# Tasmodul_WLED.net
KiCad netlist of a schematic drawn in EAGLE
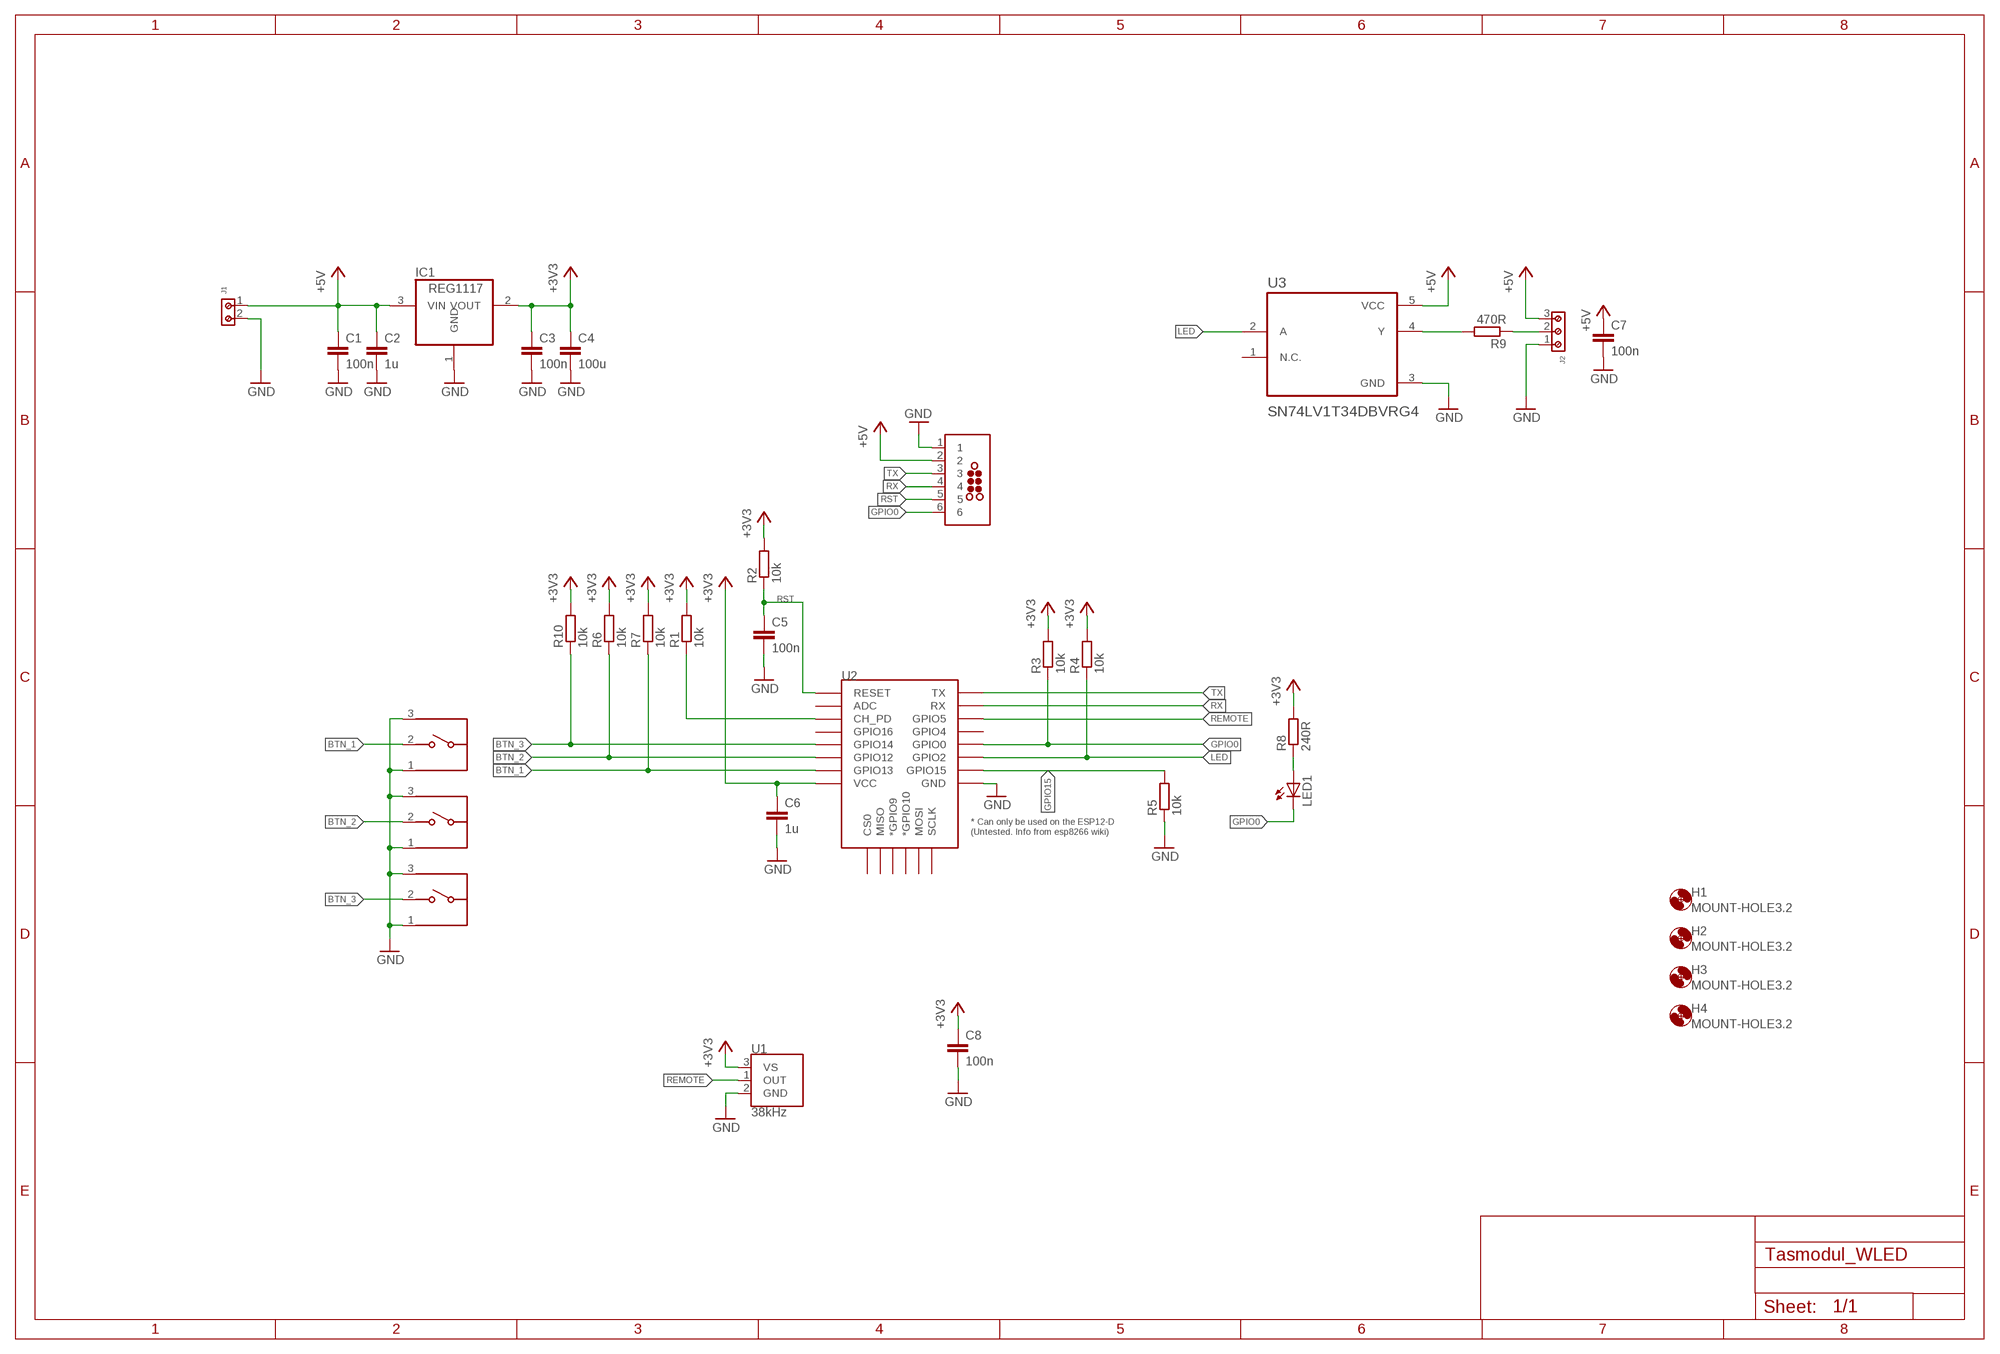
[diagram p0: schematic, sheet 1]

(export (version "E")
  (design (tool "Eeschema 10.0.6"))
  (components
    (comp (ref "C1")
      (value "100n")
      (footprint "eagle-import:C0603")
      (libsource (lib "eagle-import") (part "C-EUC0603"))
    )
    (comp (ref "C2")
      (value "1u")
      (footprint "eagle-import:C0603")
      (libsource (lib "eagle-import") (part "C-EUC0603"))
    )
    (comp (ref "C3")
      (value "100n")
      (footprint "eagle-import:C0603")
      (libsource (lib "eagle-import") (part "C-EUC0603"))
    )
    (comp (ref "C4")
      (value "100u")
      (footprint "eagle-import:C0603")
      (libsource (lib "eagle-import") (part "C-EUC0603"))
    )
    (comp (ref "C5")
      (value "100n")
      (footprint "eagle-import:C0603")
      (libsource (lib "eagle-import") (part "C-EUC0603"))
    )
    (comp (ref "C6")
      (value "1u")
      (footprint "eagle-import:C0603")
      (libsource (lib "eagle-import") (part "C-EUC0603"))
    )
    (comp (ref "C7")
      (value "100n")
      (footprint "eagle-import:C0603")
      (libsource (lib "eagle-import") (part "C-EUC0603"))
    )
    (comp (ref "C8")
      (value "100n")
      (footprint "eagle-import:C0603")
      (libsource (lib "eagle-import") (part "C-EUC0603"))
    )
    (comp (ref "H1")
      (value "MOUNT-HOLE3.2")
      (footprint "eagle-import:3,2")
      (libsource (lib "eagle-import") (part "MOUNT-HOLE3.2"))
    )
    (comp (ref "H2")
      (value "MOUNT-HOLE3.2")
      (footprint "eagle-import:3,2")
      (libsource (lib "eagle-import") (part "MOUNT-HOLE3.2"))
    )
    (comp (ref "H3")
      (value "MOUNT-HOLE3.2")
      (footprint "eagle-import:3,2")
      (libsource (lib "eagle-import") (part "MOUNT-HOLE3.2"))
    )
    (comp (ref "H4")
      (value "MOUNT-HOLE3.2")
      (footprint "eagle-import:3,2")
      (libsource (lib "eagle-import") (part "MOUNT-HOLE3.2"))
    )
    (comp (ref "IC1")
      (value "REG1117")
      (footprint "eagle-import:SOT223")
      (libsource (lib "eagle-import") (part "REG1117"))
    )
    (comp (ref "J1")
      (value "691210910002")
      (footprint "eagle-import:691210910002")
      (libsource (lib "eagle-import") (part "691210910002"))
    )
    (comp (ref "J2")
      (value "691210910003")
      (footprint "eagle-import:691210910003")
      (libsource (lib "eagle-import") (part "691210910003"))
    )
    (comp (ref "J6")
      (value "TC2030-MCP-NL")
      (footprint "eagle-import:TC2030-MCP-NL")
      (libsource (lib "eagle-import") (part "TC2030-MCP-NL"))
    )
    (comp (ref "LED1")
      (value "LEDCHIP-LED0603")
      (footprint "eagle-import:CHIP-LED0603")
      (libsource (lib "eagle-import") (part "LEDCHIP-LED0603"))
    )
    (comp (ref "R1")
      (value "10k")
      (footprint "eagle-import:R0603")
      (libsource (lib "eagle-import") (part "R-EU_R0603"))
    )
    (comp (ref "R2")
      (value "10k")
      (footprint "eagle-import:R0603")
      (libsource (lib "eagle-import") (part "R-EU_R0603"))
    )
    (comp (ref "R3")
      (value "10k")
      (footprint "eagle-import:R0603")
      (libsource (lib "eagle-import") (part "R-EU_R0603"))
    )
    (comp (ref "R4")
      (value "10k")
      (footprint "eagle-import:R0603")
      (libsource (lib "eagle-import") (part "R-EU_R0603"))
    )
    (comp (ref "R5")
      (value "10k")
      (footprint "eagle-import:R0603")
      (libsource (lib "eagle-import") (part "R-EU_R0603"))
    )
    (comp (ref "R6")
      (value "10k")
      (footprint "eagle-import:R0603")
      (libsource (lib "eagle-import") (part "R-EU_R0603"))
    )
    (comp (ref "R7")
      (value "10k")
      (footprint "eagle-import:R0603")
      (libsource (lib "eagle-import") (part "R-EU_R0603"))
    )
    (comp (ref "R8")
      (value "240R")
      (footprint "eagle-import:R0603")
      (libsource (lib "eagle-import") (part "R-EU_R0603"))
    )
    (comp (ref "R9")
      (value "470R")
      (footprint "eagle-import:R0603")
      (libsource (lib "eagle-import") (part "R-EU_R0603"))
    )
    (comp (ref "R10")
      (value "10k")
      (footprint "eagle-import:R0603")
      (libsource (lib "eagle-import") (part "R-EU_R0603"))
    )
    (comp (ref "S1")
      (value "436333033816")
      (footprint "eagle-import:436333033816")
      (libsource (lib "eagle-import") (part "436333033816"))
    )
    (comp (ref "S2")
      (value "436333033816")
      (footprint "eagle-import:436333033816")
      (libsource (lib "eagle-import") (part "436333033816"))
    )
    (comp (ref "S3")
      (value "436333033816")
      (footprint "eagle-import:436333033816")
      (libsource (lib "eagle-import") (part "436333033816"))
    )
    (comp (ref "U1")
      (value "38kHz")
      (footprint "eagle-import:TSOP382")
      (libsource (lib "eagle-import") (part "TSOP38238"))
    )
    (comp (ref "U2")
      (value "ESP12ESMD")
      (footprint "eagle-import:ESP12E-SMD")
      (libsource (lib "eagle-import") (part "ESP12ESMD"))
    )
    (comp (ref "U3")
      (value "SN74LV1T34DBVRG4")
      (footprint "eagle-import:SOT95P280X145-5N")
      (fields (field (name "MF") "Texas Instruments"))
      (libsource (lib "eagle-import") (part "SN74LV1T34DBVRG4"))
    )
  )
  (nets
    (net (code "1") (name "+3V3") (class "Default")
      (node (ref "C3") (pin "1") (pinfunction "1_1") (pintype "passive"))
      (node (ref "C4") (pin "1") (pinfunction "1_1") (pintype "passive"))
      (node (ref "C6") (pin "1") (pinfunction "1_1") (pintype "passive"))
      (node (ref "C8") (pin "1") (pinfunction "1_1") (pintype "passive"))
      (node (ref "IC1") (pin "2") (pinfunction "VOUT_2") (pintype "output"))
      (node (ref "R1") (pin "2") (pinfunction "2_2") (pintype "passive"))
      (node (ref "R10") (pin "2") (pinfunction "2_2") (pintype "passive"))
      (node (ref "R2") (pin "2") (pinfunction "2_2") (pintype "passive"))
      (node (ref "R3") (pin "2") (pinfunction "2_2") (pintype "passive"))
      (node (ref "R4") (pin "2") (pinfunction "2_2") (pintype "passive"))
      (node (ref "R6") (pin "2") (pinfunction "2_2") (pintype "passive"))
      (node (ref "R7") (pin "2") (pinfunction "2_2") (pintype "passive"))
      (node (ref "R8") (pin "2") (pinfunction "2_2") (pintype "passive"))
      (node (ref "U1") (pin "3") (pinfunction "VS_3") (pintype "bidirectional"))
      (node (ref "U2") (pin "VCC") (pinfunction "VCC_VCC") (pintype "bidirectional"))
    )
    (net (code "2") (name "+5V") (class "Default")
      (node (ref "C1") (pin "1") (pinfunction "1_1") (pintype "passive"))
      (node (ref "C2") (pin "1") (pinfunction "1_1") (pintype "passive"))
      (node (ref "C7") (pin "1") (pinfunction "1_1") (pintype "passive"))
      (node (ref "IC1") (pin "3") (pinfunction "VIN_3") (pintype "input"))
      (node (ref "J1") (pin "1") (pinfunction "1_1") (pintype "passive"))
      (node (ref "J2") (pin "3") (pinfunction "3_3") (pintype "passive"))
      (node (ref "J6") (pin "2") (pinfunction "2_2") (pintype "power_in"))
      (node (ref "U3") (pin "5") (pinfunction "VCC_5") (pintype "power_in"))
    )
    (net (code "3") (name "BTN_1") (class "Default")
      (node (ref "R7") (pin "1") (pinfunction "1_1") (pintype "passive"))
      (node (ref "S3") (pin "2") (pinfunction "2_2") (pintype "bidirectional"))
      (node (ref "U2") (pin "GPIO13") (pinfunction "GPIO13_GPIO13") (pintype "bidirectional"))
    )
    (net (code "4") (name "BTN_2") (class "Default")
      (node (ref "R6") (pin "1") (pinfunction "1_1") (pintype "passive"))
      (node (ref "S2") (pin "2") (pinfunction "2_2") (pintype "bidirectional"))
      (node (ref "U2") (pin "GPIO12") (pinfunction "GPIO12_GPIO12") (pintype "bidirectional"))
    )
    (net (code "5") (name "BTN_3") (class "Default")
      (node (ref "R10") (pin "1") (pinfunction "1_1") (pintype "passive"))
      (node (ref "S1") (pin "2") (pinfunction "2_2") (pintype "bidirectional"))
      (node (ref "U2") (pin "GPIO14") (pinfunction "GPIO14_GPIO14") (pintype "bidirectional"))
    )
    (net (code "6") (name "GND") (class "Default")
      (node (ref "C1") (pin "2") (pinfunction "2_2") (pintype "passive"))
      (node (ref "C2") (pin "2") (pinfunction "2_2") (pintype "passive"))
      (node (ref "C3") (pin "2") (pinfunction "2_2") (pintype "passive"))
      (node (ref "C4") (pin "2") (pinfunction "2_2") (pintype "passive"))
      (node (ref "C5") (pin "2") (pinfunction "2_2") (pintype "passive"))
      (node (ref "C6") (pin "2") (pinfunction "2_2") (pintype "passive"))
      (node (ref "C7") (pin "2") (pinfunction "2_2") (pintype "passive"))
      (node (ref "C8") (pin "2") (pinfunction "2_2") (pintype "passive"))
      (node (ref "IC1") (pin "1") (pinfunction "GND_1") (pintype "power_in"))
      (node (ref "J1") (pin "2") (pinfunction "2_2") (pintype "passive"))
      (node (ref "J2") (pin "1") (pinfunction "1_1") (pintype "passive"))
      (node (ref "J6") (pin "1") (pinfunction "1_1") (pintype "passive"))
      (node (ref "R5") (pin "1") (pinfunction "1_1") (pintype "passive"))
      (node (ref "S1") (pin "1") (pinfunction "1_1") (pintype "bidirectional"))
      (node (ref "S1") (pin "3") (pinfunction "3_3") (pintype "bidirectional"))
      (node (ref "S2") (pin "1") (pinfunction "1_1") (pintype "bidirectional"))
      (node (ref "S2") (pin "3") (pinfunction "3_3") (pintype "bidirectional"))
      (node (ref "S3") (pin "1") (pinfunction "1_1") (pintype "bidirectional"))
      (node (ref "S3") (pin "3") (pinfunction "3_3") (pintype "bidirectional"))
      (node (ref "U1") (pin "2") (pinfunction "GND_2") (pintype "bidirectional"))
      (node (ref "U2") (pin "GND") (pinfunction "GND_GND") (pintype "bidirectional"))
      (node (ref "U3") (pin "3") (pinfunction "GND_3") (pintype "power_in"))
    )
    (net (code "7") (name "GPIO0") (class "Default")
      (node (ref "J6") (pin "6") (pinfunction "6_6") (pintype "bidirectional"))
      (node (ref "LED1") (pin "C") (pinfunction "C_C") (pintype "passive"))
      (node (ref "R3") (pin "1") (pinfunction "1_1") (pintype "passive"))
      (node (ref "U2") (pin "GPIO0") (pinfunction "GPIO0_GPIO0") (pintype "bidirectional"))
    )
    (net (code "8") (name "GPIO15") (class "Default")
      (node (ref "R5") (pin "2") (pinfunction "2_2") (pintype "passive"))
      (node (ref "U2") (pin "GPIO15") (pinfunction "GPIO15_GPIO15") (pintype "bidirectional"))
    )
    (net (code "9") (name "LED") (class "Default")
      (node (ref "R4") (pin "1") (pinfunction "1_1") (pintype "passive"))
      (node (ref "U2") (pin "GPIO2") (pinfunction "GPIO2_GPIO2") (pintype "bidirectional"))
      (node (ref "U3") (pin "2") (pinfunction "A_2") (pintype "input"))
    )
    (net (code "10") (name "Net-(J2-Pad2)") (class "Default")
      (node (ref "J2") (pin "2") (pinfunction "2_2") (pintype "passive"))
      (node (ref "R9") (pin "1") (pinfunction "1_1") (pintype "passive"))
    )
    (net (code "11") (name "Net-(LED1-PadA)") (class "Default")
      (node (ref "LED1") (pin "A") (pinfunction "A_A") (pintype "passive"))
      (node (ref "R8") (pin "1") (pinfunction "1_1") (pintype "passive"))
    )
    (net (code "12") (name "Net-(R1-Pad1)") (class "Default")
      (node (ref "R1") (pin "1") (pinfunction "1_1") (pintype "passive"))
      (node (ref "U2") (pin "CH_PD") (pinfunction "CH_PD_CH_PD") (pintype "bidirectional"))
    )
    (net (code "13") (name "Net-(U3-Y)") (class "Default")
      (node (ref "R9") (pin "2") (pinfunction "2_2") (pintype "passive"))
      (node (ref "U3") (pin "4") (pinfunction "Y_4") (pintype "output"))
    )
    (net (code "14") (name "REMOTE") (class "Default")
      (node (ref "U1") (pin "1") (pinfunction "OUT_1") (pintype "bidirectional"))
      (node (ref "U2") (pin "GPIO5") (pinfunction "GPIO5_GPIO5") (pintype "bidirectional"))
    )
    (net (code "15") (name "RST") (class "Default")
      (node (ref "C5") (pin "1") (pinfunction "1_1") (pintype "passive"))
      (node (ref "J6") (pin "5") (pinfunction "5_5") (pintype "output"))
      (node (ref "R2") (pin "1") (pinfunction "1_1") (pintype "passive"))
      (node (ref "U2") (pin "RESET") (pinfunction "RESET_RESET") (pintype "bidirectional"))
    )
    (net (code "16") (name "RX") (class "Default")
      (node (ref "J6") (pin "4") (pinfunction "4_4") (pintype "bidirectional"))
      (node (ref "U2") (pin "RXD0") (pinfunction "RX_RXD0") (pintype "bidirectional"))
    )
    (net (code "17") (name "TX") (class "Default")
      (node (ref "J6") (pin "3") (pinfunction "3_3") (pintype "power_in"))
      (node (ref "U2") (pin "TXD0") (pinfunction "TX_TXD0") (pintype "bidirectional"))
    )
    (net (code "18") (name "unconnected-(U2-*GPIO9-PadGPIO9)") (class "Default")
      (node (ref "U2") (pin "GPIO9") (pinfunction "*GPIO9_GPIO9") (pintype "bidirectional"))
    )
    (net (code "19") (name "unconnected-(U2-*GPIO10-PadGPIO10)") (class "Default")
      (node (ref "U2") (pin "GPIO10") (pinfunction "*GPIO10_GPIO10") (pintype "bidirectional"))
    )
    (net (code "20") (name "unconnected-(U2-PadADC)") (class "Default")
      (node (ref "U2") (pin "ADC") (pinfunction "ADC_ADC") (pintype "bidirectional"))
    )
    (net (code "21") (name "unconnected-(U2-PadCS0)") (class "Default")
      (node (ref "U2") (pin "CS0") (pinfunction "CS0_CS0") (pintype "bidirectional"))
    )
    (net (code "22") (name "unconnected-(U2-PadGPIO4)") (class "Default")
      (node (ref "U2") (pin "GPIO4") (pinfunction "GPIO4_GPIO4") (pintype "bidirectional"))
    )
    (net (code "23") (name "unconnected-(U2-PadGPIO16)") (class "Default")
      (node (ref "U2") (pin "GPIO16") (pinfunction "GPIO16_GPIO16") (pintype "bidirectional"))
    )
    (net (code "24") (name "unconnected-(U2-PadMISO)") (class "Default")
      (node (ref "U2") (pin "MISO") (pinfunction "MISO_MISO") (pintype "bidirectional"))
    )
    (net (code "25") (name "unconnected-(U2-PadMOSI)") (class "Default")
      (node (ref "U2") (pin "MOSI") (pinfunction "MOSI_MOSI") (pintype "bidirectional"))
    )
    (net (code "26") (name "unconnected-(U2-PadSCLK)") (class "Default")
      (node (ref "U2") (pin "SCLK") (pinfunction "SCLK_SCLK") (pintype "bidirectional"))
    )
    (net (code "27") (name "unconnected-(U3-N.C.-Pad1)") (class "Default")
      (node (ref "U3") (pin "1") (pinfunction "N.C._1") (pintype "bidirectional"))
    )
  )
)
